# BSS_T10_Underboard_component_design.net
KiCad netlist of a schematic drawn in EAGLE
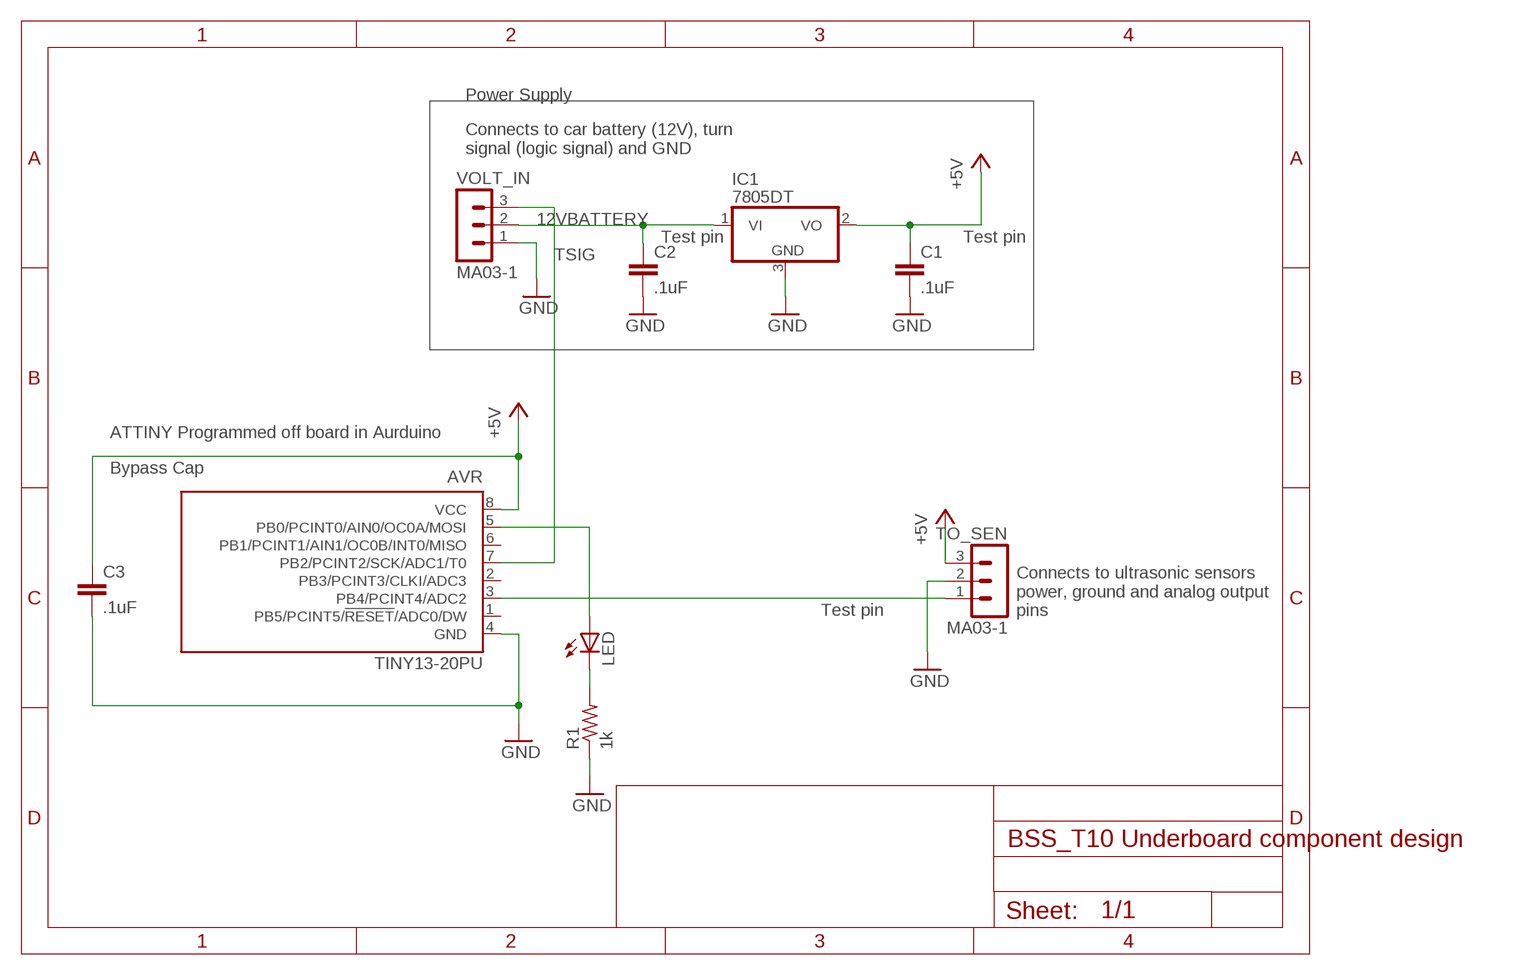
[diagram p0: schematic, sheet 1]

(export (version "E")
  (design (tool "Eeschema 10.0.6"))
  (components
    (comp (ref "AVR")
      (value "TINY13-20PU")
      (footprint "eagle-import:DIL08")
      (fields (field (name "MPN") "ATTINY13-20PU"))
      (libsource (lib "eagle-import") (part "TINY13PU-20"))
    )
    (comp (ref "C1")
      (value ".1uF")
      (footprint "eagle-import:C0805")
      (libsource (lib "eagle-import") (part "C-EUC0805"))
    )
    (comp (ref "C2")
      (value ".1uF")
      (footprint "eagle-import:C0805")
      (libsource (lib "eagle-import") (part "C-EUC0805"))
    )
    (comp (ref "C3")
      (value ".1uF")
      (footprint "eagle-import:C0805")
      (libsource (lib "eagle-import") (part "C-EUC0805"))
    )
    (comp (ref "IC1")
      (value "7805DT")
      (footprint "eagle-import:TO252")
      (libsource (lib "eagle-import") (part "78DT05"))
    )
    (comp (ref "LED")
      (value "LED5MM")
      (footprint "eagle-import:LED5MM")
      (libsource (lib "eagle-import") (part "LED5MM"))
    )
    (comp (ref "R1")
      (value "1k")
      (footprint "eagle-import:R0805")
      (libsource (lib "eagle-import") (part "R-US_R0805"))
    )
    (comp (ref "TO_SEN")
      (value "MA03-1")
      (footprint "eagle-import:MA03-1")
      (libsource (lib "eagle-import") (part "MA03-1"))
    )
    (comp (ref "VOLT_IN")
      (value "MA03-1")
      (footprint "eagle-import:MA03-1")
      (libsource (lib "eagle-import") (part "MA03-1"))
    )
  )
  (nets
    (net (code "1") (name "+5V") (class "Default")
      (node (ref "AVR") (pin "8") (pinfunction "VCC_8") (pintype "power_in"))
      (node (ref "C1") (pin "1") (pinfunction "1_1") (pintype "passive"))
      (node (ref "C3") (pin "1") (pinfunction "1_1") (pintype "passive"))
      (node (ref "IC1") (pin "2") (pinfunction "VO_2") (pintype "passive"))
      (node (ref "TO_SEN") (pin "3") (pinfunction "3_3") (pintype "passive"))
    )
    (net (code "2") (name "/12VBATTERY") (class "Default")
      (node (ref "C2") (pin "1") (pinfunction "1_1") (pintype "passive"))
      (node (ref "IC1") (pin "1") (pinfunction "VI_1") (pintype "input"))
      (node (ref "VOLT_IN") (pin "2") (pinfunction "2_2") (pintype "passive"))
    )
    (net (code "3") (name "/TSIG") (class "Default")
      (node (ref "AVR") (pin "7") (pinfunction "PB2/PCINT2/SCK/ADC1/T0_7") (pintype "bidirectional"))
      (node (ref "VOLT_IN") (pin "3") (pinfunction "3_3") (pintype "passive"))
    )
    (net (code "4") (name "GND") (class "Default")
      (node (ref "AVR") (pin "4") (pinfunction "GND_4") (pintype "power_in"))
      (node (ref "C1") (pin "2") (pinfunction "2_2") (pintype "passive"))
      (node (ref "C2") (pin "2") (pinfunction "2_2") (pintype "passive"))
      (node (ref "C3") (pin "2") (pinfunction "2_2") (pintype "passive"))
      (node (ref "IC1") (pin "3") (pinfunction "GND_3") (pintype "passive"))
      (node (ref "R1") (pin "1") (pinfunction "1_1") (pintype "passive"))
      (node (ref "TO_SEN") (pin "2") (pinfunction "2_2") (pintype "passive"))
      (node (ref "VOLT_IN") (pin "1") (pinfunction "1_1") (pintype "passive"))
    )
    (net (code "5") (name "Net-(AVR-PB0{slash}PCINT0{slash}AIN0{slash}OC0A{slash}MOSI)") (class "Default")
      (node (ref "AVR") (pin "5") (pinfunction "PB0/PCINT0/AIN0/OC0A/MOSI_5") (pintype "bidirectional"))
      (node (ref "LED") (pin "A") (pinfunction "A_A") (pintype "passive"))
    )
    (net (code "6") (name "Net-(AVR-PB4{slash}PCINT4{slash}ADC2)") (class "Default")
      (node (ref "AVR") (pin "3") (pinfunction "PB4/PCINT4/ADC2_3") (pintype "bidirectional"))
      (node (ref "TO_SEN") (pin "1") (pinfunction "1_1") (pintype "passive"))
    )
    (net (code "7") (name "Net-(LED-C)") (class "Default")
      (node (ref "LED") (pin "K") (pinfunction "C_K") (pintype "passive"))
      (node (ref "R1") (pin "2") (pinfunction "2_2") (pintype "passive"))
    )
    (net (code "8") (name "unconnected-(AVR-PB1{slash}PCINT1{slash}AIN1{slash}OC0B{slash}INT0{slash}MISO-Pad6)") (class "Default")
      (node (ref "AVR") (pin "6") (pinfunction "PB1/PCINT1/AIN1/OC0B/INT0/MISO_6") (pintype "bidirectional"))
    )
    (net (code "9") (name "unconnected-(AVR-PB3{slash}PCINT3{slash}CLKI{slash}ADC3-Pad2)") (class "Default")
      (node (ref "AVR") (pin "2") (pinfunction "PB3/PCINT3/CLKI/ADC3_2") (pintype "bidirectional"))
    )
    (net (code "10") (name "unconnected-(AVR-PB5{slash}PCINT5{slash}~{RESET}{slash}ADC0{slash}DW-Pad1)") (class "Default")
      (node (ref "AVR") (pin "1") (pinfunction "PB5/PCINT5/~{RESET}/ADC0/DW_1") (pintype "bidirectional"))
    )
  )
)
